# ProPrj_ENPHY-PCB-PROJECT-EN1B_2026-05-29.net
KiCad netlist of a schematic drawn in EasyEDA Pro
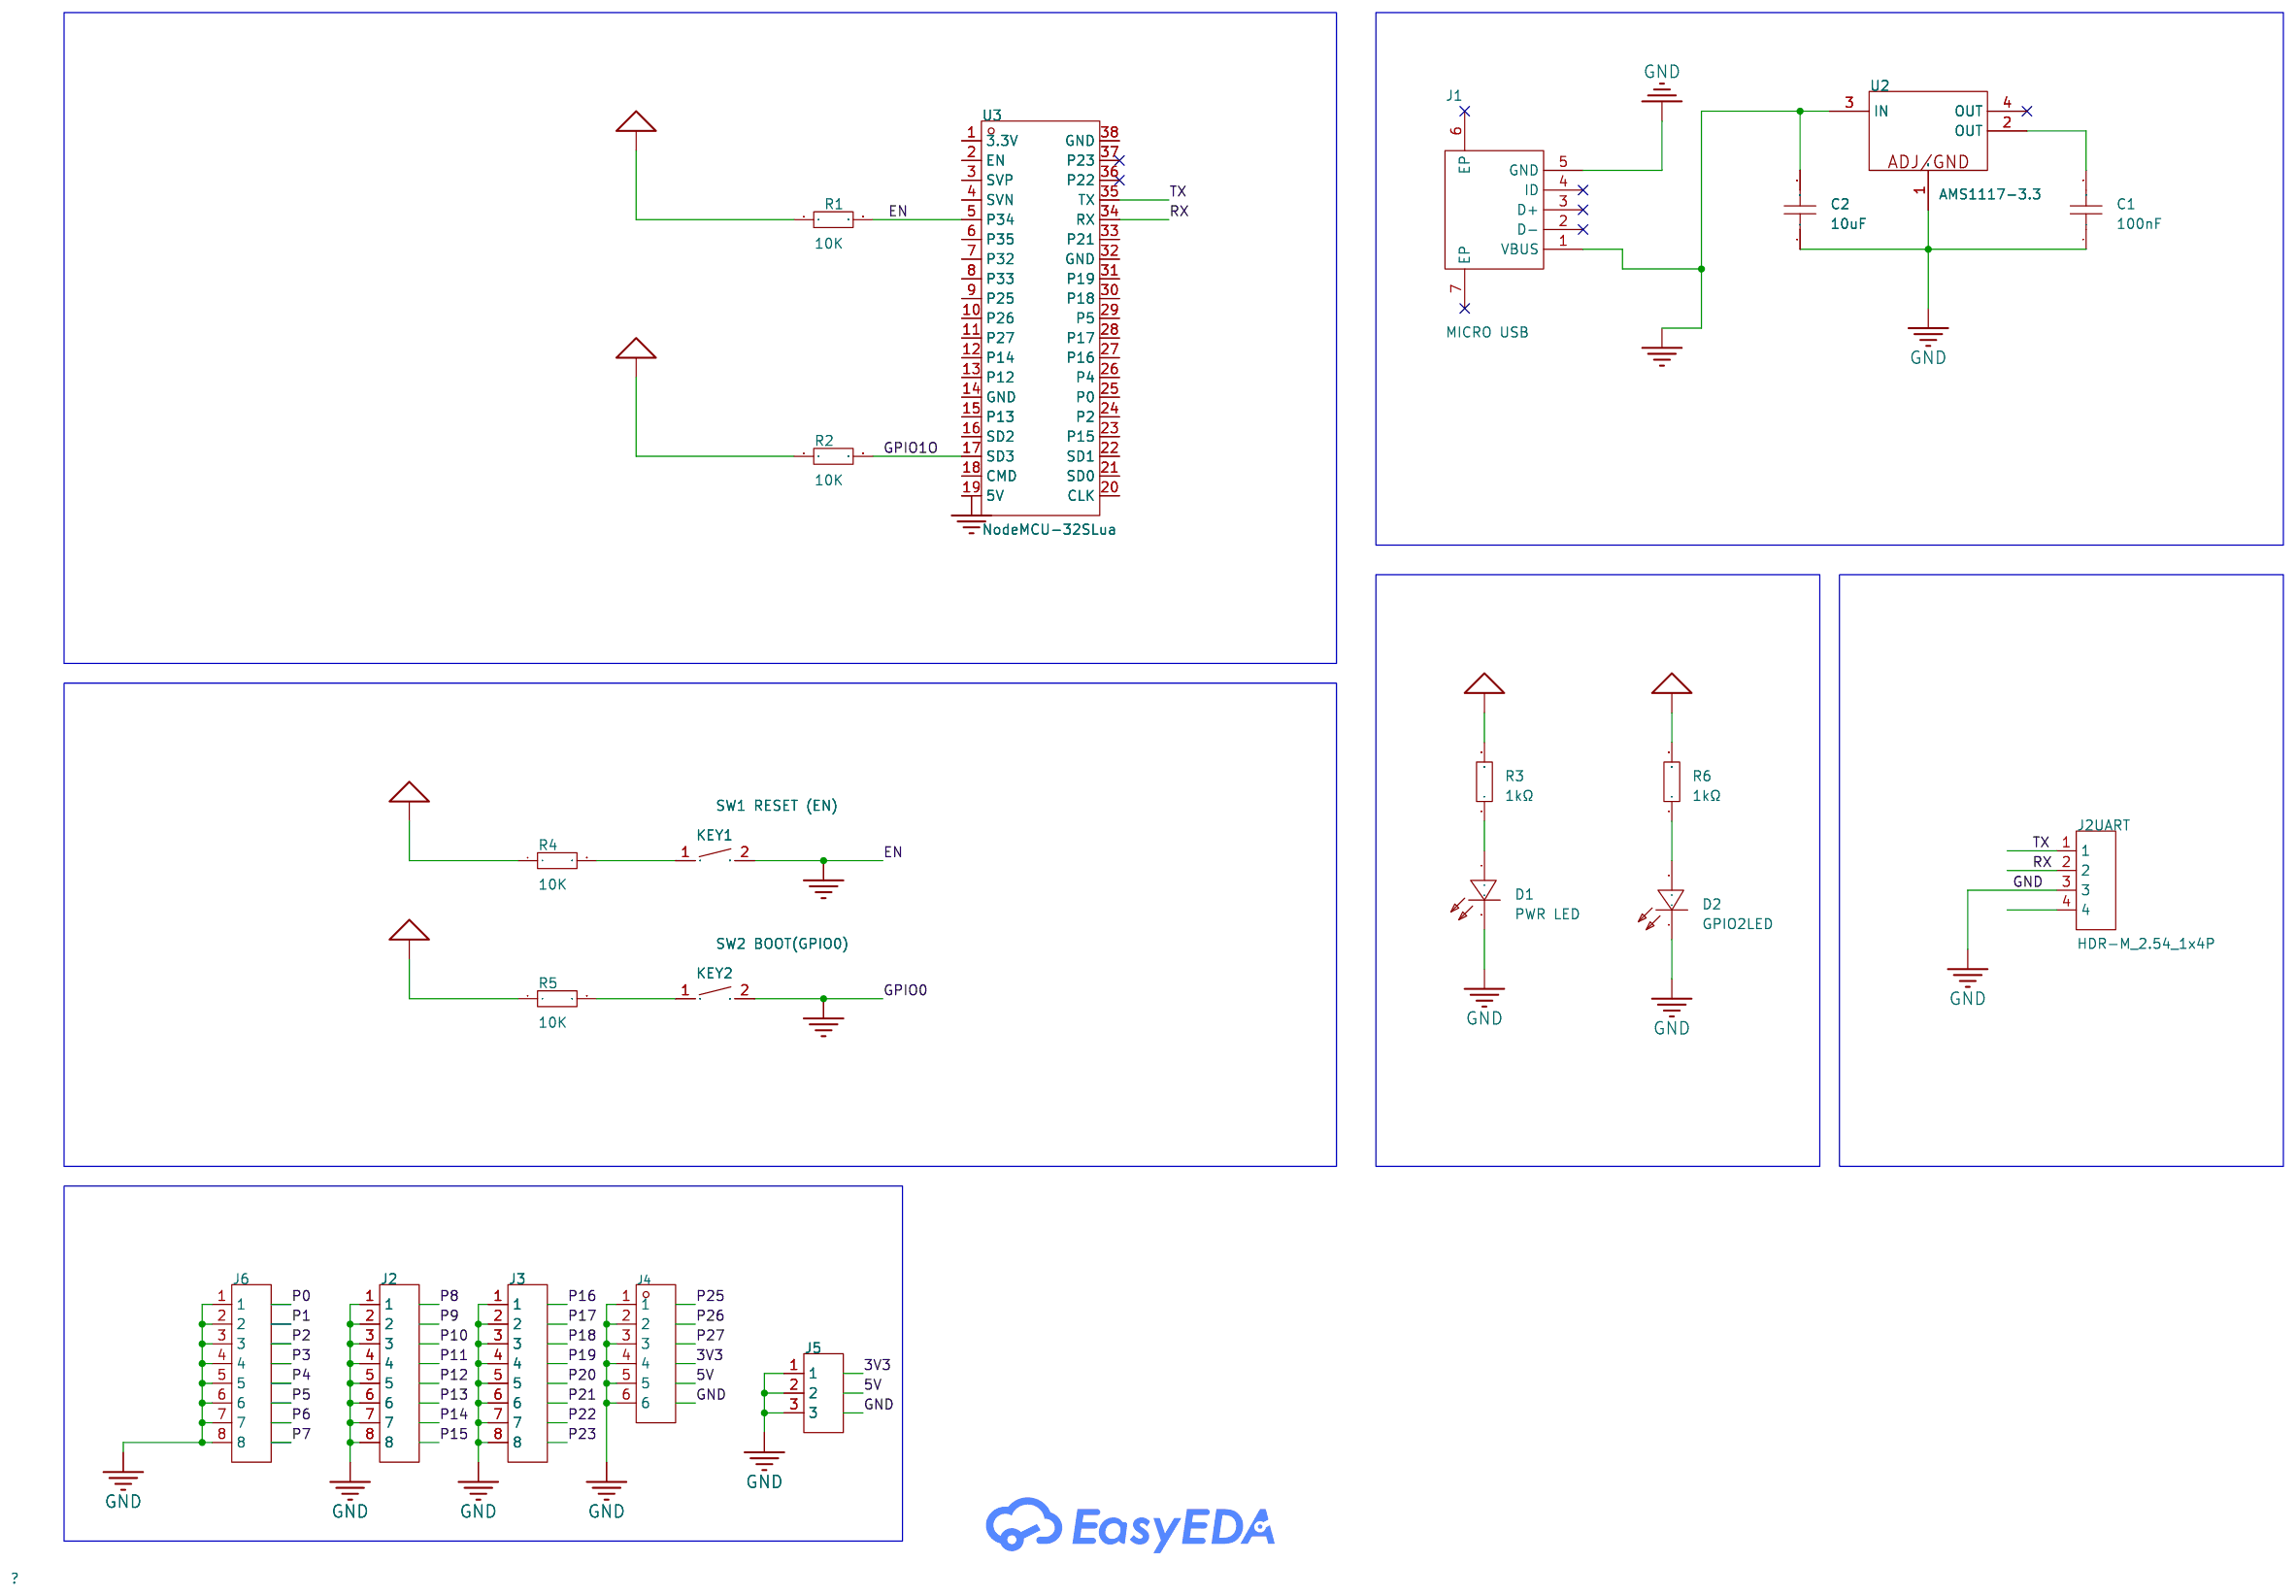
[diagram p0: schematic sheet]

(export (version "E")
  (design (tool "Eeschema 10.0.6"))
  (components
    (comp (ref "C1")
      (value "100nF")
      (footprint "easyedapro:C0603")
      (description "Capacitance:100nF Tolerance:±10% Tolerance:±10% Voltage Rating:50V Temperature Coefficient:X7R")
      (fields
        (field (name "Manufacturer Part") "CC0603KRX7R9BB104")
        (field (name "Manufacturer") "YAGEO(国巨)")
      )
      (libsource (lib "easyedapro") (part "CC0603KRX7R9BB104"))
    )
    (comp (ref "C2")
      (value "10uF")
      (footprint "easyedapro:C0603")
      (description "Capacitance:10uF Tolerance:±10% Tolerance:±10% Voltage Rating:10V Temperature Coefficient:X5R")
      (fields
        (field (name "Manufacturer Part") "CL10A106KP8NNNC")
        (field (name "Manufacturer") "SAMSUNG(三星)")
      )
      (libsource (lib "easyedapro") (part "CL10A106KP8NNNC"))
    )
    (comp (ref "D1")
      (value "PWR LED")
      (footprint "easyedapro:LED0603-R-RD")
      (fields (field (name "Manufacturer Part") "LED0603-R"))
      (libsource (lib "easyedapro") (part "LED0603-R"))
    )
    (comp (ref "D2")
      (value "GPIO2LED")
      (footprint "easyedapro:LED0603-R-RD_WHITE")
      (fields (field (name "Manufacturer Part") "KT-0603W") (field (name "Manufacturer") "KENTO"))
      (libsource (lib "easyedapro") (part "0603White light_C2290"))
    )
    (comp (ref "J1")
      (value "MICRO USB")
      (footprint "easyedapro:USB-MICRO_USB-MICRO-5P")
      (fields (field (name "Manufacturer Part") "USB-Micro-5p"))
      (libsource (lib "easyedapro") (part "USB-MICRO-5P_C9900014940"))
    )
    (comp (ref "J2")
      (value "~")
      (footprint "easyedapro:HDR-TH_8P-P2.54-V-F-1")
      (libsource (lib "easyedapro") (part "Header-Female-2.54_1x8"))
    )
    (comp (ref "J2UART")
      (value "HDR-M_2.54_1x4P")
      (footprint "easyedapro:HDR-TH_HDR-M_2.54_1X4P")
      (libsource (lib "easyedapro") (part "HDR-M_2.54_1X4P"))
    )
    (comp (ref "J3")
      (value "~")
      (footprint "easyedapro:HDR-TH_8P-P2.54-V-F-1")
      (libsource (lib "easyedapro") (part "Header-Female-2.54_1x8"))
    )
    (comp (ref "J4")
      (value "~")
      (footprint "easyedapro:HDR-TH_6P-P2.54-V-F")
      (libsource (lib "easyedapro") (part "Header-Female-2.54_1x6"))
    )
    (comp (ref "J5")
      (value "~")
      (footprint "easyedapro:HDR-TH_3P-P2.54-V-F")
      (libsource (lib "easyedapro") (part "PM254V-11-03-H85"))
    )
    (comp (ref "J6")
      (value "~")
      (footprint "easyedapro:HDR-TH_8P-P2.54-V-F-1")
      (libsource (lib "easyedapro") (part "Header-Female-2.54_1x8"))
    )
    (comp (ref "KEY1")
      (value "SW1 RESET (EN)")
      (footprint "easyedapro:KEY-SMD_L4.0-W3.0-LS4.9-1")
      (fields (field (name "Manufacturer Part") "SWITCH,TACT,1.57N,3.9X2.9MM"))
      (libsource (lib "easyedapro") (part "SWITCH,TACT,1.57N,3.9X2.9MM"))
    )
    (comp (ref "KEY2")
      (value "SW2 BOOT(GPIO0)")
      (footprint "easyedapro:KEY-SMD_L4.0-W3.0-LS4.9-1")
      (fields (field (name "Manufacturer Part") "SWITCH,TACT,1.57N,3.9X2.9MM"))
      (libsource (lib "easyedapro") (part "SWITCH,TACT,1.57N,3.9X2.9MM"))
    )
    (comp (ref "R1") (value "10K") (footprint "easyedapro:R0603") (libsource (lib "easyedapro") (part "Res")))
    (comp (ref "R2") (value "10K") (footprint "easyedapro:R0603") (libsource (lib "easyedapro") (part "Res")))
    (comp (ref "R3")
      (value "1kΩ")
      (footprint "easyedapro:R0603")
      (fields
        (field (name "Manufacturer Part") "0603WAF1001T5E")
        (field (name "Manufacturer") "UNI-ROYAL(厚声)")
      )
      (libsource (lib "easyedapro") (part "0603WAF1001T5E"))
    )
    (comp (ref "R4") (value "10K") (footprint "easyedapro:R0603") (libsource (lib "easyedapro") (part "Res")))
    (comp (ref "R5") (value "10K") (footprint "easyedapro:R0603") (libsource (lib "easyedapro") (part "Res")))
    (comp (ref "R6")
      (value "1kΩ")
      (footprint "easyedapro:R0805")
      (fields
        (field (name "Manufacturer Part") "0805W8F1001T5E")
        (field (name "Manufacturer") "UNI-ROYAL(厚声)")
      )
      (libsource (lib "easyedapro") (part "0805W8F1001T5E"))
    )
    (comp (ref "U2")
      (value "AMS1117-3.3")
      (footprint "easyedapro:SOT-223-3_L6.4-W3.5-P2.30-LS7.0-BR")
      (fields (field (name "Manufacturer") "国芯佳品"))
      (libsource (lib "easyedapro") (part "AMS1117-3.3_C2992570"))
    )
    (comp (ref "U3")
      (value "NodeMCU-32SLua")
      (footprint "easyedapro:COMM-TH_NODEMCU-32SLUA")
      (fields (field (name "Manufacturer") "Ai-Thinker(安信可)"))
      (libsource (lib "easyedapro") (part "NODEMCU-32SLUA"))
    )
  )
  (nets
    (net (code "1") (name "/GPIO1O") (class "Default")
      (node (ref "R2") (pin "2") (pinfunction "2_2") (pintype "input"))
      (node (ref "U3") (pin "17") (pinfunction "SD3_17") (pintype "input"))
    )
    (net (code "29") (name "/RX") (class "Default")
      (node (ref "J2UART") (pin "2") (pinfunction "2_2") (pintype "unspecified"))
      (node (ref "U3") (pin "34") (pinfunction "RX_34") (pintype "input"))
    )
    (net (code "30") (name "/TX") (class "Default")
      (node (ref "J2UART") (pin "1") (pinfunction "1_1") (pintype "unspecified"))
      (node (ref "U3") (pin "35") (pinfunction "TX_35") (pintype "input"))
    )
    (net (code "31") (name "3V3") (class "Default")
      (node (ref "R1") (pin "1") (pinfunction "1_1") (pintype "input"))
      (node (ref "R2") (pin "1") (pinfunction "1_1") (pintype "input"))
      (node (ref "R3") (pin "2") (pinfunction "2_2") (pintype "input"))
      (node (ref "R4") (pin "1") (pinfunction "1_1") (pintype "input"))
      (node (ref "R5") (pin "1") (pinfunction "1_1") (pintype "input"))
      (node (ref "U3") (pin "19") (pinfunction "5V_19") (pintype "input"))
    )
    (net (code "32") (name "5V") (class "Default")
      (node (ref "C2") (pin "2") (pinfunction "2_2") (pintype "unspecified"))
      (node (ref "J1") (pin "1") (pinfunction "VBUS_1") (pintype "unspecified"))
      (node (ref "U2") (pin "3") (pinfunction "IN_3") (pintype "unspecified"))
    )
    (net (code "33") (name "EN") (class "Default")
      (node (ref "KEY1") (pin "2") (pinfunction "2_2") (pintype "unspecified"))
      (node (ref "R1") (pin "2") (pinfunction "2_2") (pintype "input"))
      (node (ref "U3") (pin "5") (pinfunction "P34_5") (pintype "input"))
    )
    (net (code "34") (name "GND") (class "Default")
      (node (ref "C1") (pin "1") (pinfunction "1_1") (pintype "unspecified"))
      (node (ref "C2") (pin "1") (pinfunction "1_1") (pintype "unspecified"))
      (node (ref "D1") (pin "2") (pinfunction "K_2") (pintype "unspecified"))
      (node (ref "D2") (pin "2") (pinfunction "K_2") (pintype "unspecified"))
      (node (ref "J1") (pin "5") (pinfunction "GND_5") (pintype "unspecified"))
      (node (ref "J2") (pin "1") (pinfunction "1_1") (pintype "unspecified"))
      (node (ref "J2") (pin "2") (pinfunction "2_2") (pintype "unspecified"))
      (node (ref "J2") (pin "3") (pinfunction "3_3") (pintype "unspecified"))
      (node (ref "J2") (pin "4") (pinfunction "4_4") (pintype "unspecified"))
      (node (ref "J2") (pin "5") (pinfunction "5_5") (pintype "unspecified"))
      (node (ref "J2") (pin "6") (pinfunction "6_6") (pintype "unspecified"))
      (node (ref "J2") (pin "7") (pinfunction "7_7") (pintype "unspecified"))
      (node (ref "J2") (pin "8") (pinfunction "8_8") (pintype "unspecified"))
      (node (ref "J2UART") (pin "3") (pinfunction "3_3") (pintype "unspecified"))
      (node (ref "J3") (pin "1") (pinfunction "1_1") (pintype "unspecified"))
      (node (ref "J3") (pin "2") (pinfunction "2_2") (pintype "unspecified"))
      (node (ref "J3") (pin "3") (pinfunction "3_3") (pintype "unspecified"))
      (node (ref "J3") (pin "4") (pinfunction "4_4") (pintype "unspecified"))
      (node (ref "J3") (pin "5") (pinfunction "5_5") (pintype "unspecified"))
      (node (ref "J3") (pin "6") (pinfunction "6_6") (pintype "unspecified"))
      (node (ref "J3") (pin "7") (pinfunction "7_7") (pintype "unspecified"))
      (node (ref "J3") (pin "8") (pinfunction "8_8") (pintype "unspecified"))
      (node (ref "J4") (pin "1") (pinfunction "1_1") (pintype "input"))
      (node (ref "J4") (pin "2") (pinfunction "2_2") (pintype "input"))
      (node (ref "J4") (pin "3") (pinfunction "3_3") (pintype "input"))
      (node (ref "J4") (pin "4") (pinfunction "4_4") (pintype "input"))
      (node (ref "J4") (pin "5") (pinfunction "5_5") (pintype "input"))
      (node (ref "J4") (pin "6") (pinfunction "6_6") (pintype "input"))
      (node (ref "J5") (pin "1") (pinfunction "1_1") (pintype "unspecified"))
      (node (ref "J5") (pin "2") (pinfunction "2_2") (pintype "unspecified"))
      (node (ref "J5") (pin "3") (pinfunction "3_3") (pintype "unspecified"))
      (node (ref "J6") (pin "1") (pinfunction "1_1") (pintype "unspecified"))
      (node (ref "J6") (pin "2") (pinfunction "2_2") (pintype "unspecified"))
      (node (ref "J6") (pin "3") (pinfunction "3_3") (pintype "unspecified"))
      (node (ref "J6") (pin "4") (pinfunction "4_4") (pintype "unspecified"))
      (node (ref "J6") (pin "5") (pinfunction "5_5") (pintype "unspecified"))
      (node (ref "J6") (pin "6") (pinfunction "6_6") (pintype "unspecified"))
      (node (ref "J6") (pin "7") (pinfunction "7_7") (pintype "unspecified"))
      (node (ref "J6") (pin "8") (pinfunction "8_8") (pintype "unspecified"))
      (node (ref "U2") (pin "1") (pinfunction "ADJ/GND_1") (pintype "unspecified"))
    )
    (net (code "35") (name "GPIO0") (class "Default")
      (node (ref "KEY2") (pin "2") (pinfunction "2_2") (pintype "unspecified"))
    )
    (net (code "36") (name "GPIO2") (class "Default")
      (node (ref "R6") (pin "2") (pinfunction "2_2") (pintype "input"))
    )
    (net (code "37") (name "Net-(C1-Pad2)") (class "Default")
      (node (ref "C1") (pin "2") (pinfunction "2_2") (pintype "unspecified"))
      (node (ref "U2") (pin "2") (pinfunction "OUT_2") (pintype "unspecified"))
    )
    (net (code "38") (name "Net-(D1-A)") (class "Default")
      (node (ref "D1") (pin "1") (pinfunction "A_1") (pintype "unspecified"))
      (node (ref "R3") (pin "1") (pinfunction "1_1") (pintype "input"))
    )
    (net (code "39") (name "Net-(D2-A)") (class "Default")
      (node (ref "D2") (pin "1") (pinfunction "A_1") (pintype "unspecified"))
      (node (ref "R6") (pin "1") (pinfunction "1_1") (pintype "input"))
    )
    (net (code "40") (name "Net-(KEY1-Pad1)") (class "Default")
      (node (ref "KEY1") (pin "1") (pinfunction "1_1") (pintype "unspecified"))
      (node (ref "R4") (pin "2") (pinfunction "2_2") (pintype "input"))
    )
    (net (code "41") (name "Net-(KEY2-Pad1)") (class "Default")
      (node (ref "KEY2") (pin "1") (pinfunction "1_1") (pintype "unspecified"))
      (node (ref "R5") (pin "2") (pinfunction "2_2") (pintype "input"))
    )
    (net (code "42") (name "unconnected-(J1-D+-Pad3)") (class "Default")
      (node (ref "J1") (pin "3") (pinfunction "D+_3") (pintype "unspecified+no_connect"))
    )
    (net (code "43") (name "unconnected-(J1-D--Pad2)") (class "Default")
      (node (ref "J1") (pin "2") (pinfunction "D-_2") (pintype "unspecified+no_connect"))
    )
    (net (code "44") (name "unconnected-(J1-EP-Pad6)") (class "Default")
      (node (ref "J1") (pin "6") (pinfunction "EP_6") (pintype "unspecified+no_connect"))
    )
    (net (code "45") (name "unconnected-(J1-EP-Pad7)") (class "Default")
      (node (ref "J1") (pin "7") (pinfunction "EP_7") (pintype "unspecified+no_connect"))
    )
    (net (code "46") (name "unconnected-(J1-ID-Pad4)") (class "Default")
      (node (ref "J1") (pin "4") (pinfunction "ID_4") (pintype "unspecified+no_connect"))
    )
    (net (code "47") (name "unconnected-(J2UART-Pad4)") (class "Default")
      (node (ref "J2UART") (pin "4") (pinfunction "4_4") (pintype "unspecified"))
    )
    (net (code "48") (name "unconnected-(U2-OUT-Pad4)") (class "Default")
      (node (ref "U2") (pin "4") (pinfunction "OUT_4") (pintype "unspecified+no_connect"))
    )
    (net (code "49") (name "unconnected-(U3-3.3V-Pad1)") (class "Default")
      (node (ref "U3") (pin "1") (pinfunction "3.3V_1") (pintype "input"))
    )
    (net (code "50") (name "unconnected-(U3-CLK-Pad20)") (class "Default")
      (node (ref "U3") (pin "20") (pinfunction "CLK_20") (pintype "input"))
    )
    (net (code "51") (name "unconnected-(U3-CMD-Pad18)") (class "Default")
      (node (ref "U3") (pin "18") (pinfunction "CMD_18") (pintype "input"))
    )
    (net (code "52") (name "unconnected-(U3-EN-Pad2)") (class "Default")
      (node (ref "U3") (pin "2") (pinfunction "EN_2") (pintype "input"))
    )
    (net (code "53") (name "unconnected-(U3-GND-Pad14)") (class "Default")
      (node (ref "U3") (pin "14") (pinfunction "GND_14") (pintype "input"))
    )
    (net (code "54") (name "unconnected-(U3-GND-Pad32)") (class "Default")
      (node (ref "U3") (pin "32") (pinfunction "GND_32") (pintype "input"))
    )
    (net (code "55") (name "unconnected-(U3-GND-Pad38)") (class "Default")
      (node (ref "U3") (pin "38") (pinfunction "GND_38") (pintype "input"))
    )
    (net (code "56") (name "unconnected-(U3-P0-Pad25)") (class "Default")
      (node (ref "U3") (pin "25") (pinfunction "P0_25") (pintype "input"))
    )
    (net (code "57") (name "unconnected-(U3-P2-Pad24)") (class "Default")
      (node (ref "U3") (pin "24") (pinfunction "P2_24") (pintype "input"))
    )
    (net (code "58") (name "unconnected-(U3-P4-Pad26)") (class "Default")
      (node (ref "U3") (pin "26") (pinfunction "P4_26") (pintype "input"))
    )
    (net (code "59") (name "unconnected-(U3-P5-Pad29)") (class "Default")
      (node (ref "U3") (pin "29") (pinfunction "P5_29") (pintype "input"))
    )
    (net (code "60") (name "unconnected-(U3-P12-Pad13)") (class "Default")
      (node (ref "U3") (pin "13") (pinfunction "P12_13") (pintype "input"))
    )
    (net (code "61") (name "unconnected-(U3-P13-Pad15)") (class "Default")
      (node (ref "U3") (pin "15") (pinfunction "P13_15") (pintype "input"))
    )
    (net (code "62") (name "unconnected-(U3-P14-Pad12)") (class "Default")
      (node (ref "U3") (pin "12") (pinfunction "P14_12") (pintype "input"))
    )
    (net (code "63") (name "unconnected-(U3-P15-Pad23)") (class "Default")
      (node (ref "U3") (pin "23") (pinfunction "P15_23") (pintype "input"))
    )
    (net (code "64") (name "unconnected-(U3-P16-Pad27)") (class "Default")
      (node (ref "U3") (pin "27") (pinfunction "P16_27") (pintype "input"))
    )
    (net (code "65") (name "unconnected-(U3-P17-Pad28)") (class "Default")
      (node (ref "U3") (pin "28") (pinfunction "P17_28") (pintype "input"))
    )
    (net (code "66") (name "unconnected-(U3-P18-Pad30)") (class "Default")
      (node (ref "U3") (pin "30") (pinfunction "P18_30") (pintype "input"))
    )
    (net (code "67") (name "unconnected-(U3-P19-Pad31)") (class "Default")
      (node (ref "U3") (pin "31") (pinfunction "P19_31") (pintype "input"))
    )
    (net (code "68") (name "unconnected-(U3-P21-Pad33)") (class "Default")
      (node (ref "U3") (pin "33") (pinfunction "P21_33") (pintype "input"))
    )
    (net (code "69") (name "unconnected-(U3-P22-Pad36)") (class "Default")
      (node (ref "U3") (pin "36") (pinfunction "P22_36") (pintype "input+no_connect"))
    )
    (net (code "70") (name "unconnected-(U3-P23-Pad37)") (class "Default")
      (node (ref "U3") (pin "37") (pinfunction "P23_37") (pintype "input+no_connect"))
    )
    (net (code "71") (name "unconnected-(U3-P25-Pad9)") (class "Default")
      (node (ref "U3") (pin "9") (pinfunction "P25_9") (pintype "input"))
    )
    (net (code "72") (name "unconnected-(U3-P26-Pad10)") (class "Default")
      (node (ref "U3") (pin "10") (pinfunction "P26_10") (pintype "input"))
    )
    (net (code "73") (name "unconnected-(U3-P27-Pad11)") (class "Default")
      (node (ref "U3") (pin "11") (pinfunction "P27_11") (pintype "input"))
    )
    (net (code "74") (name "unconnected-(U3-P32-Pad7)") (class "Default")
      (node (ref "U3") (pin "7") (pinfunction "P32_7") (pintype "input"))
    )
    (net (code "75") (name "unconnected-(U3-P33-Pad8)") (class "Default")
      (node (ref "U3") (pin "8") (pinfunction "P33_8") (pintype "input"))
    )
    (net (code "76") (name "unconnected-(U3-P35-Pad6)") (class "Default")
      (node (ref "U3") (pin "6") (pinfunction "P35_6") (pintype "input"))
    )
    (net (code "77") (name "unconnected-(U3-SD0-Pad21)") (class "Default")
      (node (ref "U3") (pin "21") (pinfunction "SD0_21") (pintype "input"))
    )
    (net (code "78") (name "unconnected-(U3-SD1-Pad22)") (class "Default")
      (node (ref "U3") (pin "22") (pinfunction "SD1_22") (pintype "input"))
    )
    (net (code "79") (name "unconnected-(U3-SD2-Pad16)") (class "Default")
      (node (ref "U3") (pin "16") (pinfunction "SD2_16") (pintype "input"))
    )
    (net (code "80") (name "unconnected-(U3-SVN-Pad4)") (class "Default")
      (node (ref "U3") (pin "4") (pinfunction "SVN_4") (pintype "input"))
    )
    (net (code "81") (name "unconnected-(U3-SVP-Pad3)") (class "Default")
      (node (ref "U3") (pin "3") (pinfunction "SVP_3") (pintype "input"))
    )
  )
)
